# Digital.net
KiCad netlist of a schematic drawn in EAGLE
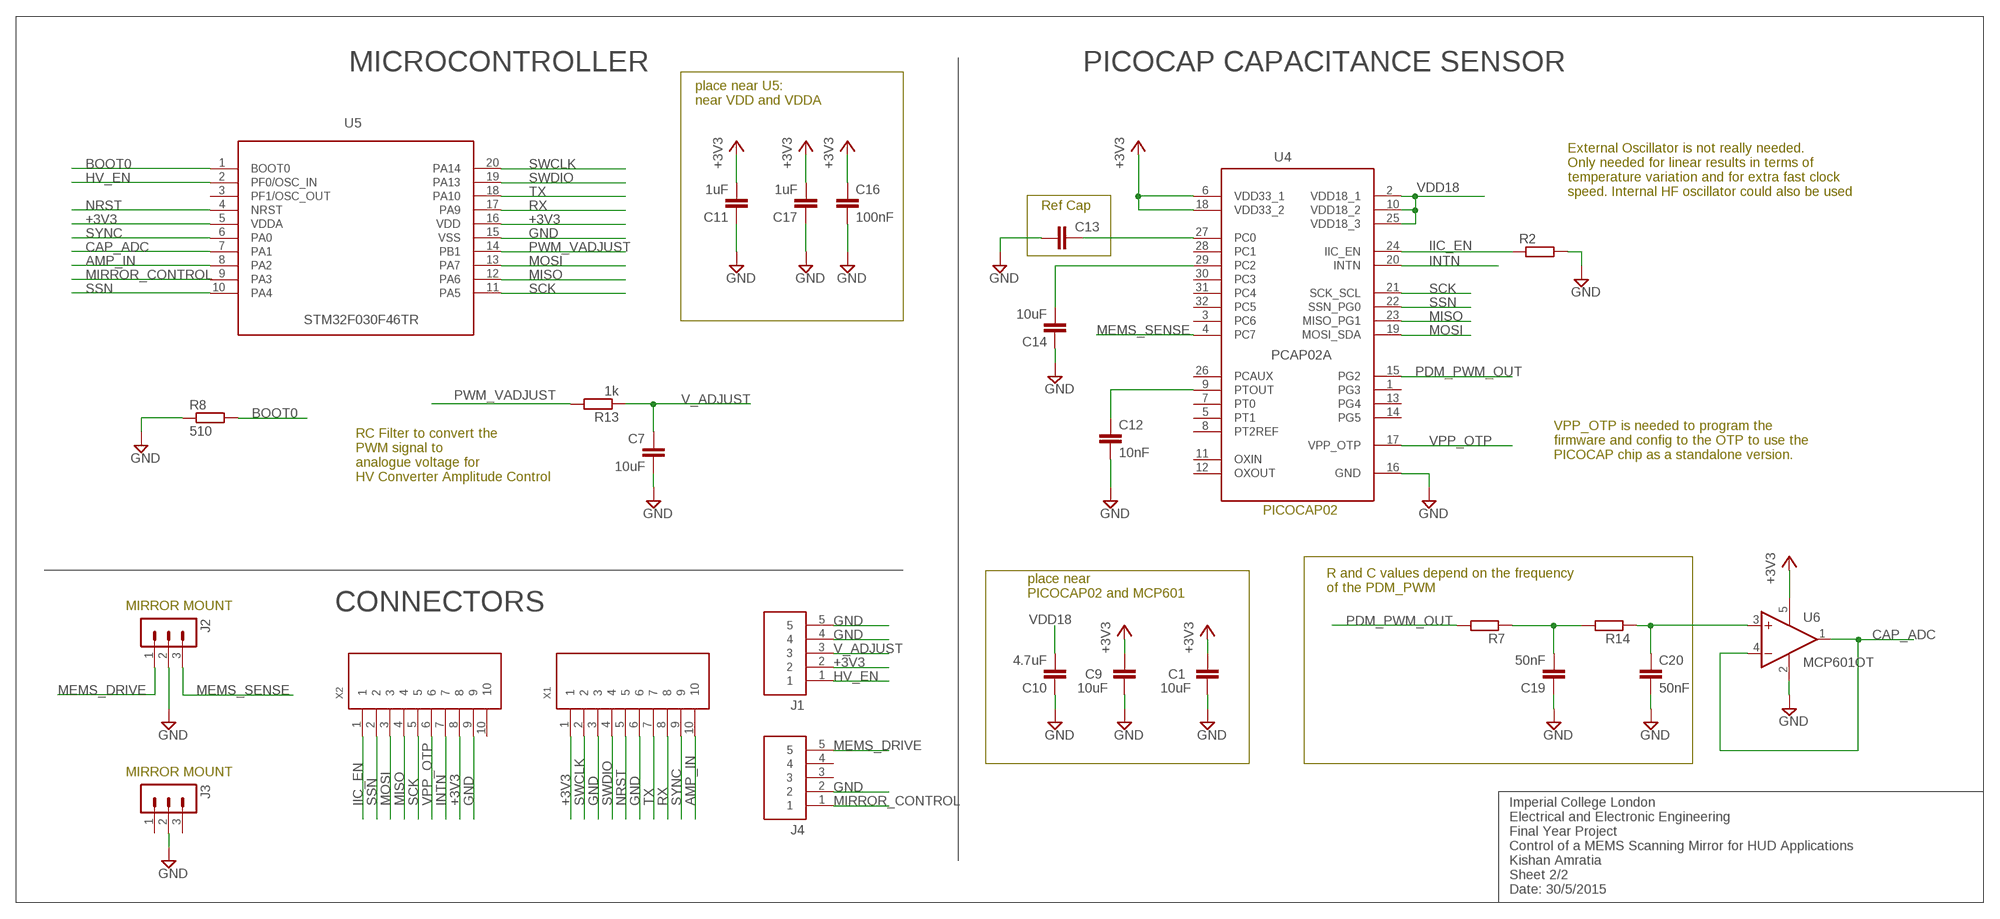
[diagram p0: schematic, sheet 1]

(export (version "E")
  (design (tool "Eeschema 10.0.6"))
  (components
    (comp (ref "C1")
      (value "10uF")
      (footprint "eagle-import:C0603K")
      (libsource (lib "eagle-import") (part "C-EUC0603K"))
    )
    (comp (ref "C7")
      (value "10uF")
      (footprint "eagle-import:C0603")
      (libsource (lib "eagle-import") (part "C-EUC0603"))
    )
    (comp (ref "C9")
      (value "10uF")
      (footprint "eagle-import:C0603K")
      (libsource (lib "eagle-import") (part "C-EUC0603K"))
    )
    (comp (ref "C10")
      (value "4.7uF")
      (footprint "eagle-import:C0603K")
      (libsource (lib "eagle-import") (part "C-EUC0603K"))
    )
    (comp (ref "C11")
      (value "1uF")
      (footprint "eagle-import:C0603K")
      (libsource (lib "eagle-import") (part "C-EUC0603K"))
    )
    (comp (ref "C12")
      (value "10nF")
      (footprint "eagle-import:C0603K")
      (libsource (lib "eagle-import") (part "C-EUC0603K"))
    )
    (comp (ref "C13")
      (value "C-EUC0603K")
      (footprint "eagle-import:C0603K")
      (libsource (lib "eagle-import") (part "C-EUC0603K"))
    )
    (comp (ref "C14")
      (value "10uF")
      (footprint "eagle-import:C0603K")
      (libsource (lib "eagle-import") (part "C-EUC0603K"))
    )
    (comp (ref "C16")
      (value "100nF")
      (footprint "eagle-import:C0603K")
      (libsource (lib "eagle-import") (part "C-EUC0603K"))
    )
    (comp (ref "C17")
      (value "1uF")
      (footprint "eagle-import:C0603K")
      (libsource (lib "eagle-import") (part "C-EUC0603K"))
    )
    (comp (ref "C19")
      (value "50nF")
      (footprint "eagle-import:C0603K")
      (libsource (lib "eagle-import") (part "C-EUC0603K"))
    )
    (comp (ref "C20")
      (value "50nF")
      (footprint "eagle-import:C0603K")
      (libsource (lib "eagle-import") (part "C-EUC0603K"))
    )
    (comp (ref "J1")
      (value "1.27MM_5WAY_HEADER")
      (footprint "eagle-import:1.27MM_5WAY_HEADER")
      (libsource (lib "eagle-import") (part "1.27MM_5WAY_HEADER"))
    )
    (comp (ref "J2")
      (value "MA03-1")
      (footprint "eagle-import:MA03-1")
      (libsource (lib "eagle-import") (part "MA03-1"))
    )
    (comp (ref "J3")
      (value "MA03-1")
      (footprint "eagle-import:MA03-1")
      (libsource (lib "eagle-import") (part "MA03-1"))
    )
    (comp (ref "J4")
      (value "1.27MM_5WAY_HEADER")
      (footprint "eagle-import:1.27MM_5WAY_HEADER")
      (libsource (lib "eagle-import") (part "1.27MM_5WAY_HEADER"))
    )
    (comp (ref "R2")
      (value "R-EU_R0603")
      (footprint "eagle-import:R0603")
      (libsource (lib "eagle-import") (part "R-EU_R0603"))
    )
    (comp (ref "R7")
      (value "R-EU_R0603")
      (footprint "eagle-import:R0603")
      (libsource (lib "eagle-import") (part "R-EU_R0603"))
    )
    (comp (ref "R8")
      (value "510")
      (footprint "eagle-import:R0603")
      (libsource (lib "eagle-import") (part "R-EU_R0603"))
    )
    (comp (ref "R13")
      (value "1k")
      (footprint "eagle-import:R0603")
      (libsource (lib "eagle-import") (part "R-EU_R0603"))
    )
    (comp (ref "R14")
      (value "R-EU_R0603")
      (footprint "eagle-import:R0603")
      (libsource (lib "eagle-import") (part "R-EU_R0603"))
    )
    (comp (ref "U4")
      (value "PCAP02A")
      (footprint "eagle-import:QFN32")
      (libsource (lib "eagle-import") (part "PCAP02A"))
    )
    (comp (ref "U5")
      (value "STM32F030XX")
      (footprint "eagle-import:TSOP20")
      (libsource (lib "eagle-import") (part "STM32F030XX"))
    )
    (comp (ref "U6")
      (value "MCP601OT")
      (footprint "eagle-import:SOT23-5")
      (libsource (lib "eagle-import") (part "MCP601OT"))
    )
    (comp (ref "X1")
      (value "OMRON_FPC_0.5MM_10WAY")
      (footprint "eagle-import:OMRON_FPC_0.5MM_10WAY")
      (libsource (lib "eagle-import") (part "OMRON_FPC_0.5MM_10WAY"))
    )
    (comp (ref "X2")
      (value "OMRON_FPC_0.5MM_10WAY")
      (footprint "eagle-import:OMRON_FPC_0.5MM_10WAY")
      (libsource (lib "eagle-import") (part "OMRON_FPC_0.5MM_10WAY"))
    )
  )
  (nets
    (net (code "1") (name "+3V3") (class "Default")
      (node (ref "C1") (pin "1") (pinfunction "1_1") (pintype "passive"))
      (node (ref "C11") (pin "2") (pinfunction "2_2") (pintype "passive"))
      (node (ref "C16") (pin "1") (pinfunction "1_1") (pintype "passive"))
      (node (ref "C17") (pin "2") (pinfunction "2_2") (pintype "passive"))
      (node (ref "C9") (pin "1") (pinfunction "1_1") (pintype "passive"))
      (node (ref "J1") (pin "2") (pinfunction "2_2") (pintype "bidirectional"))
      (node (ref "U4") (pin "18") (pinfunction "VDD33_2_18") (pintype "power_in"))
      (node (ref "U4") (pin "6") (pinfunction "VDD33_1_6") (pintype "power_in"))
      (node (ref "U5") (pin "16") (pinfunction "VDD_16") (pintype "bidirectional"))
      (node (ref "U5") (pin "5") (pinfunction "VDDA_5") (pintype "bidirectional"))
      (node (ref "U6") (pin "5") (pinfunction "V+_5") (pintype "power_in"))
      (node (ref "X1") (pin "1") (pinfunction "1_1") (pintype "bidirectional"))
      (node (ref "X2") (pin "8") (pinfunction "8_8") (pintype "bidirectional"))
    )
    (net (code "2") (name "/AMP_IN") (class "Default")
      (node (ref "U5") (pin "8") (pinfunction "PA2_8") (pintype "bidirectional"))
      (node (ref "X1") (pin "10") (pinfunction "10_10") (pintype "bidirectional"))
    )
    (net (code "3") (name "/BOOT0") (class "Default")
      (node (ref "R8") (pin "2") (pinfunction "2_2") (pintype "passive"))
      (node (ref "U5") (pin "1") (pinfunction "BOOT0_1") (pintype "bidirectional"))
    )
    (net (code "4") (name "/CAP_ADC") (class "Default")
      (node (ref "U5") (pin "7") (pinfunction "PA1_7") (pintype "bidirectional"))
      (node (ref "U6") (pin "1") (pinfunction "OUT_1") (pintype "output"))
      (node (ref "U6") (pin "4") (pinfunction "-IN_4") (pintype "input"))
    )
    (net (code "5") (name "/HV_EN") (class "Default")
      (node (ref "J1") (pin "1") (pinfunction "1_1") (pintype "bidirectional"))
      (node (ref "U5") (pin "2") (pinfunction "PF0/OSC_IN_2") (pintype "bidirectional"))
    )
    (net (code "6") (name "/IIC_EN") (class "Default")
      (node (ref "R2") (pin "1") (pinfunction "1_1") (pintype "passive"))
      (node (ref "U4") (pin "24") (pinfunction "IIC_EN_24") (pintype "input"))
      (node (ref "X2") (pin "1") (pinfunction "1_1") (pintype "bidirectional"))
    )
    (net (code "7") (name "/INTN") (class "Default")
      (node (ref "U4") (pin "20") (pinfunction "INTN_20") (pintype "output"))
      (node (ref "X2") (pin "7") (pinfunction "7_7") (pintype "bidirectional"))
    )
    (net (code "8") (name "/MEMS_DRIVE") (class "Default")
      (node (ref "J2") (pin "1") (pinfunction "1_1") (pintype "passive"))
      (node (ref "J4") (pin "5") (pinfunction "5_5") (pintype "bidirectional"))
    )
    (net (code "9") (name "/MEMS_SENSE") (class "Default")
      (node (ref "J2") (pin "3") (pinfunction "3_3") (pintype "passive"))
      (node (ref "U4") (pin "4") (pinfunction "PC7_4") (pintype "bidirectional"))
    )
    (net (code "10") (name "/MIRROR_CONTROL") (class "Default")
      (node (ref "J4") (pin "1") (pinfunction "1_1") (pintype "bidirectional"))
      (node (ref "U5") (pin "9") (pinfunction "PA3_9") (pintype "bidirectional"))
    )
    (net (code "11") (name "/MISO") (class "Default")
      (node (ref "U4") (pin "23") (pinfunction "MISO_PG1_23") (pintype "bidirectional"))
      (node (ref "U5") (pin "12") (pinfunction "PA6_12") (pintype "bidirectional"))
      (node (ref "X2") (pin "4") (pinfunction "4_4") (pintype "bidirectional"))
    )
    (net (code "12") (name "/MOSI") (class "Default")
      (node (ref "U4") (pin "19") (pinfunction "MOSI_SDA_19") (pintype "bidirectional"))
      (node (ref "U5") (pin "13") (pinfunction "PA7_13") (pintype "bidirectional"))
      (node (ref "X2") (pin "3") (pinfunction "3_3") (pintype "bidirectional"))
    )
    (net (code "13") (name "/NRST") (class "Default")
      (node (ref "U5") (pin "4") (pinfunction "NRST_4") (pintype "bidirectional"))
      (node (ref "X1") (pin "5") (pinfunction "5_5") (pintype "bidirectional"))
    )
    (net (code "14") (name "/PDM_PWM_OUT") (class "Default")
      (node (ref "R7") (pin "2") (pinfunction "2_2") (pintype "passive"))
      (node (ref "U4") (pin "15") (pinfunction "PG2_15") (pintype "bidirectional"))
    )
    (net (code "15") (name "/PWM_VADJUST") (class "Default")
      (node (ref "R13") (pin "2") (pinfunction "2_2") (pintype "passive"))
      (node (ref "U5") (pin "14") (pinfunction "PB1_14") (pintype "bidirectional"))
    )
    (net (code "16") (name "/RX") (class "Default")
      (node (ref "U5") (pin "17") (pinfunction "PA9_17") (pintype "bidirectional"))
      (node (ref "X1") (pin "8") (pinfunction "8_8") (pintype "bidirectional"))
    )
    (net (code "17") (name "/SCK") (class "Default")
      (node (ref "U4") (pin "21") (pinfunction "SCK_SCL_21") (pintype "bidirectional"))
      (node (ref "U5") (pin "11") (pinfunction "PA5_11") (pintype "bidirectional"))
      (node (ref "X2") (pin "5") (pinfunction "5_5") (pintype "bidirectional"))
    )
    (net (code "18") (name "/SSN") (class "Default")
      (node (ref "U4") (pin "22") (pinfunction "SSN_PG0_22") (pintype "bidirectional"))
      (node (ref "U5") (pin "10") (pinfunction "PA4_10") (pintype "bidirectional"))
      (node (ref "X2") (pin "2") (pinfunction "2_2") (pintype "bidirectional"))
    )
    (net (code "19") (name "/SWCLK") (class "Default")
      (node (ref "U5") (pin "20") (pinfunction "PA14_20") (pintype "bidirectional"))
      (node (ref "X1") (pin "2") (pinfunction "2_2") (pintype "bidirectional"))
    )
    (net (code "20") (name "/SWDIO") (class "Default")
      (node (ref "U5") (pin "19") (pinfunction "PA13_19") (pintype "bidirectional"))
      (node (ref "X1") (pin "4") (pinfunction "4_4") (pintype "bidirectional"))
    )
    (net (code "21") (name "/SYNC") (class "Default")
      (node (ref "U5") (pin "6") (pinfunction "PA0_6") (pintype "bidirectional"))
      (node (ref "X1") (pin "9") (pinfunction "9_9") (pintype "bidirectional"))
    )
    (net (code "22") (name "/TX") (class "Default")
      (node (ref "U5") (pin "18") (pinfunction "PA10_18") (pintype "bidirectional"))
      (node (ref "X1") (pin "7") (pinfunction "7_7") (pintype "bidirectional"))
    )
    (net (code "23") (name "/VDD18") (class "Default")
      (node (ref "C10") (pin "2") (pinfunction "2_2") (pintype "passive"))
      (node (ref "U4") (pin "10") (pinfunction "VDD18_2_10") (pintype "bidirectional"))
      (node (ref "U4") (pin "2") (pinfunction "VDD18_1_2") (pintype "bidirectional"))
      (node (ref "U4") (pin "25") (pinfunction "VDD18_3_25") (pintype "bidirectional"))
    )
    (net (code "24") (name "/VPP_OTP") (class "Default")
      (node (ref "U4") (pin "17") (pinfunction "VPP_OTP_17") (pintype "bidirectional"))
      (node (ref "X2") (pin "6") (pinfunction "6_6") (pintype "bidirectional"))
    )
    (net (code "25") (name "/V_ADJUST") (class "Default")
      (node (ref "C7") (pin "1") (pinfunction "1_1") (pintype "passive"))
      (node (ref "J1") (pin "3") (pinfunction "3_3") (pintype "bidirectional"))
      (node (ref "R13") (pin "1") (pinfunction "1_1") (pintype "passive"))
    )
    (net (code "26") (name "GND") (class "Default")
      (node (ref "C1") (pin "2") (pinfunction "2_2") (pintype "passive"))
      (node (ref "C10") (pin "1") (pinfunction "1_1") (pintype "passive"))
      (node (ref "C11") (pin "1") (pinfunction "1_1") (pintype "passive"))
      (node (ref "C12") (pin "2") (pinfunction "2_2") (pintype "passive"))
      (node (ref "C13") (pin "1") (pinfunction "1_1") (pintype "passive"))
      (node (ref "C14") (pin "1") (pinfunction "1_1") (pintype "passive"))
      (node (ref "C16") (pin "2") (pinfunction "2_2") (pintype "passive"))
      (node (ref "C17") (pin "1") (pinfunction "1_1") (pintype "passive"))
      (node (ref "C19") (pin "1") (pinfunction "1_1") (pintype "passive"))
      (node (ref "C20") (pin "2") (pinfunction "2_2") (pintype "passive"))
      (node (ref "C7") (pin "2") (pinfunction "2_2") (pintype "passive"))
      (node (ref "C9") (pin "2") (pinfunction "2_2") (pintype "passive"))
      (node (ref "J1") (pin "4") (pinfunction "4_4") (pintype "bidirectional"))
      (node (ref "J1") (pin "5") (pinfunction "5_5") (pintype "bidirectional"))
      (node (ref "J2") (pin "2") (pinfunction "2_2") (pintype "passive"))
      (node (ref "J3") (pin "2") (pinfunction "2_2") (pintype "passive"))
      (node (ref "J4") (pin "2") (pinfunction "2_2") (pintype "bidirectional"))
      (node (ref "R2") (pin "2") (pinfunction "2_2") (pintype "passive"))
      (node (ref "R8") (pin "1") (pinfunction "1_1") (pintype "passive"))
      (node (ref "U4") (pin "16") (pinfunction "GND_16") (pintype "power_in"))
      (node (ref "U5") (pin "15") (pinfunction "VSS_15") (pintype "bidirectional"))
      (node (ref "U6") (pin "2") (pinfunction "V-_2") (pintype "power_in"))
      (node (ref "X1") (pin "3") (pinfunction "3_3") (pintype "bidirectional"))
      (node (ref "X1") (pin "6") (pinfunction "6_6") (pintype "bidirectional"))
      (node (ref "X2") (pin "9") (pinfunction "9_9") (pintype "bidirectional"))
    )
    (net (code "27") (name "Net-(C19-Pad2)") (class "Default")
      (node (ref "C19") (pin "2") (pinfunction "2_2") (pintype "passive"))
      (node (ref "R14") (pin "2") (pinfunction "2_2") (pintype "passive"))
      (node (ref "R7") (pin "1") (pinfunction "1_1") (pintype "passive"))
    )
    (net (code "28") (name "Net-(U4-PC0)") (class "Default")
      (node (ref "C13") (pin "2") (pinfunction "2_2") (pintype "passive"))
      (node (ref "U4") (pin "27") (pinfunction "PC0_27") (pintype "bidirectional"))
    )
    (net (code "29") (name "Net-(U4-PC2)") (class "Default")
      (node (ref "C14") (pin "2") (pinfunction "2_2") (pintype "passive"))
      (node (ref "U4") (pin "29") (pinfunction "PC2_29") (pintype "bidirectional"))
    )
    (net (code "30") (name "Net-(U4-PTOUT)") (class "Default")
      (node (ref "C12") (pin "1") (pinfunction "1_1") (pintype "passive"))
      (node (ref "U4") (pin "9") (pinfunction "PTOUT_9") (pintype "bidirectional"))
    )
    (net (code "31") (name "Net-(U6-+IN)") (class "Default")
      (node (ref "C20") (pin "1") (pinfunction "1_1") (pintype "passive"))
      (node (ref "R14") (pin "1") (pinfunction "1_1") (pintype "passive"))
      (node (ref "U6") (pin "3") (pinfunction "+IN_3") (pintype "input"))
    )
    (net (code "32") (name "unconnected-(J3-Pad1)") (class "Default")
      (node (ref "J3") (pin "1") (pinfunction "1_1") (pintype "passive"))
    )
    (net (code "33") (name "unconnected-(J3-Pad3)") (class "Default")
      (node (ref "J3") (pin "3") (pinfunction "3_3") (pintype "passive"))
    )
    (net (code "34") (name "unconnected-(J4-Pad3)") (class "Default")
      (node (ref "J4") (pin "3") (pinfunction "3_3") (pintype "bidirectional"))
    )
    (net (code "35") (name "unconnected-(J4-Pad4)") (class "Default")
      (node (ref "J4") (pin "4") (pinfunction "4_4") (pintype "bidirectional"))
    )
    (net (code "36") (name "unconnected-(U4-OXIN-Pad11)") (class "Default")
      (node (ref "U4") (pin "11") (pinfunction "OXIN_11") (pintype "bidirectional"))
    )
    (net (code "37") (name "unconnected-(U4-OXOUT-Pad12)") (class "Default")
      (node (ref "U4") (pin "12") (pinfunction "OXOUT_12") (pintype "bidirectional"))
    )
    (net (code "38") (name "unconnected-(U4-PC1-Pad28)") (class "Default")
      (node (ref "U4") (pin "28") (pinfunction "PC1_28") (pintype "bidirectional"))
    )
    (net (code "39") (name "unconnected-(U4-PC3-Pad30)") (class "Default")
      (node (ref "U4") (pin "30") (pinfunction "PC3_30") (pintype "bidirectional"))
    )
    (net (code "40") (name "unconnected-(U4-PC4-Pad31)") (class "Default")
      (node (ref "U4") (pin "31") (pinfunction "PC4_31") (pintype "bidirectional"))
    )
    (net (code "41") (name "unconnected-(U4-PC5-Pad32)") (class "Default")
      (node (ref "U4") (pin "32") (pinfunction "PC5_32") (pintype "bidirectional"))
    )
    (net (code "42") (name "unconnected-(U4-PC6-Pad3)") (class "Default")
      (node (ref "U4") (pin "3") (pinfunction "PC6_3") (pintype "bidirectional"))
    )
    (net (code "43") (name "unconnected-(U4-PCAUX-Pad26)") (class "Default")
      (node (ref "U4") (pin "26") (pinfunction "PCAUX_26") (pintype "bidirectional"))
    )
    (net (code "44") (name "unconnected-(U4-PG3-Pad1)") (class "Default")
      (node (ref "U4") (pin "1") (pinfunction "PG3_1") (pintype "bidirectional"))
    )
    (net (code "45") (name "unconnected-(U4-PG4-Pad13)") (class "Default")
      (node (ref "U4") (pin "13") (pinfunction "PG4_13") (pintype "output"))
    )
    (net (code "46") (name "unconnected-(U4-PG5-Pad14)") (class "Default")
      (node (ref "U4") (pin "14") (pinfunction "PG5_14") (pintype "output"))
    )
    (net (code "47") (name "unconnected-(U4-PT0-Pad7)") (class "Default")
      (node (ref "U4") (pin "7") (pinfunction "PT0_7") (pintype "bidirectional"))
    )
    (net (code "48") (name "unconnected-(U4-PT1-Pad5)") (class "Default")
      (node (ref "U4") (pin "5") (pinfunction "PT1_5") (pintype "bidirectional"))
    )
    (net (code "49") (name "unconnected-(U4-PT2REF-Pad8)") (class "Default")
      (node (ref "U4") (pin "8") (pinfunction "PT2REF_8") (pintype "bidirectional"))
    )
    (net (code "50") (name "unconnected-(U5-PF1{slash}OSC_OUT-Pad3)") (class "Default")
      (node (ref "U5") (pin "3") (pinfunction "PF1/OSC_OUT_3") (pintype "bidirectional"))
    )
    (net (code "51") (name "unconnected-(X2-Pad10)") (class "Default")
      (node (ref "X2") (pin "10") (pinfunction "10_10") (pintype "bidirectional"))
    )
  )
)
